# EC800M_CN.net
KiCad netlist of a schematic drawn in Altium Designer
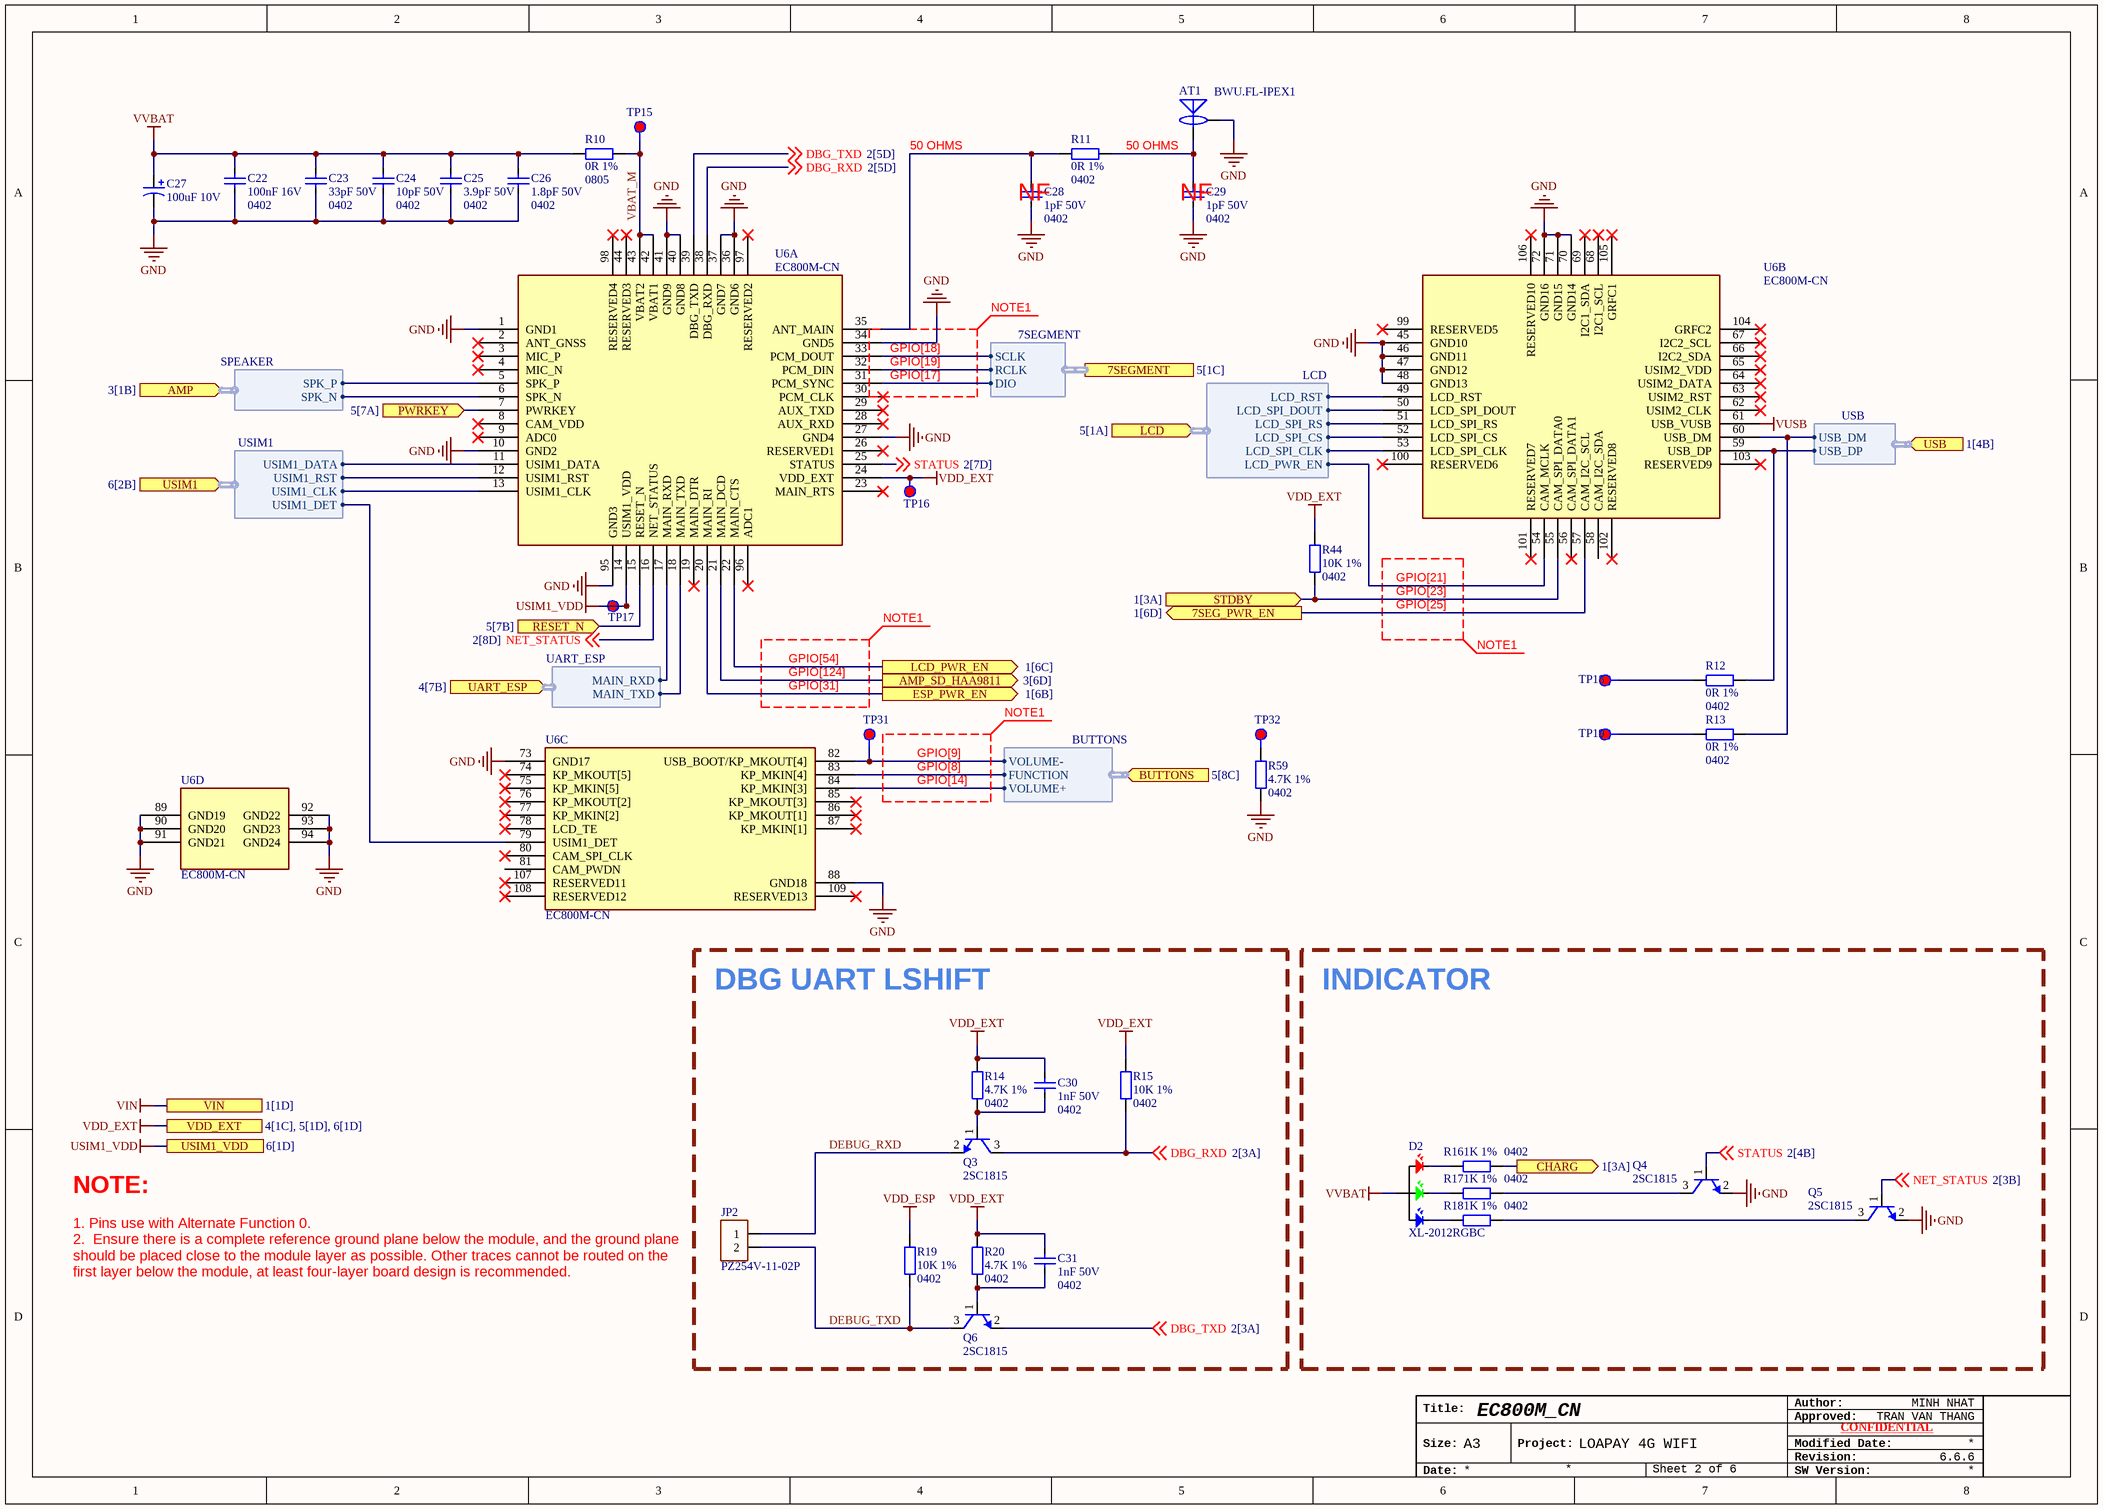
[diagram p0: EC800M_CN.SchDoc]

(export (version "E")
  (design (tool "Eeschema 10.0.6"))
  (components
    (comp (ref "AT1")
      (value "BWU.FL-IPEX1")
      (footprint "IPEX-SMD_BWIPX-1-001E")
      (description "1 Inner pin IPEX Board-End 1.25mm 6GHz 50Ω 2mm SMD Coaxial Connectors (RF) ROHS")
      (fields (field (name "MANUFACTURER") "BAT WIRELESS") (field (name "LCSC PART") "C5137195"))
      (libsource (lib "Antenna") (part "BAT WIRELESS BWU.FL-IPEX1"))
    )
    (comp (ref "C22")
      (value "100nF 16V")
      (footprint "C0402_2")
      (description "16V 100nF X7R ±10% 0402 Multilayer Ceramic Capacitors MLCC - SMD/SMT ROHS")
      (fields
        (field (name "MANUFACTURER") "YAGEO")
        (field (name "MANUFACTURE PART NUMBER") "CC0402KRX7R7BB104")
        (field (name "PACKAGE") "0402")
      )
      (libsource (lib "Capacitor") (part "C0402_MLCC_100nF_16V"))
    )
    (comp (ref "C23")
      (value "33pF 50V")
      (footprint "C0402_2")
      (description "50V 33pF NP0 ±5% 0402 Multilayer Ceramic Capacitors MLCC - SMD/SMT ROHS")
      (fields
        (field (name "MANUFACTURER") "YAGEO")
        (field (name "MANUFACTURE PART NUMBER") "CC0402JRNPO9BN330")
        (field (name "PACKAGE") "0402")
      )
      (libsource (lib "Capacitor") (part "C0402_MLCC_33pF_50V"))
    )
    (comp (ref "C24")
      (value "10pF 50V")
      (footprint "C0402_2")
      (description "50V 10pF C0G ±5% 0402 Multilayer Ceramic Capacitors MLCC - SMD/SMT ROHS")
      (fields
        (field (name "MANUFACTURER") "VIIYONG")
        (field (name "MANUFACTURE PART NUMBER") "V100J0402C0G500NBT")
        (field (name "PACKAGE") "0402")
      )
      (libsource (lib "Capacitor") (part "C0402_MLCC_10pF_50V"))
    )
    (comp (ref "C25")
      (value "3.9pF 50V")
      (footprint "C0402_2")
      (description "50V 3.9pF NP0 0402 Multilayer Ceramic Capacitors MLCC - SMD/SMT ROHS")
      (fields
        (field (name "MANUFACTURER") "YAGEO")
        (field (name "MANUFACTURE PART NUMBER") "CC0402BRNPO9BN3R9")
        (field (name "PACKAGE") "0402")
      )
      (libsource (lib "Capacitor") (part "C0402_MLCC_3.9pF_50V"))
    )
    (comp (ref "C26")
      (value "1.8pF 50V")
      (footprint "C0402_2")
      (description "50V 1.8pF C0G 0402 Multilayer Ceramic Capacitors MLCC - SMD/SMT ROHS")
      (fields
        (field (name "MANUFACTURER") "Murata Electronics")
        (field (name "MANUFACTURE PART NUMBER") "GJM1555C1H1R8WB01D")
        (field (name "PACKAGE") "0402")
      )
      (libsource (lib "Capacitor") (part "C0402_MLCC_1.8pF_50V"))
    )
    (comp (ref "C27")
      (value "100uF 10V")
      (footprint "CAP-ALU-SMD-C-NEW")
      (description "100uF 10V 49mA@120Hz ±20% SMD,D5xL5.4mm Aluminum Electrolytic Capacitors - SMD ROHS")
      (fields
        (field (name "MANUFACTURER") "ROQANG")
        (field (name "MANUFACTURE PART NUMBER") "CS1A101M-CRD54")
      )
      (libsource (lib "Capacitor") (part "C_ALU_100uF_10V_C"))
    )
    (comp (ref "C28")
      (value "1pF 50V")
      (footprint "C0402_2")
      (description "50V 1pF NP0 0402 Multilayer Ceramic Capacitors MLCC - SMD/SMT ROHS")
      (fields
        (field (name "MANUFACTURER") "Walsin Tech Corp")
        (field (name "MANUFACTURE PART NUMBER") "0402N1R0B500CT")
        (field (name "PACKAGE") "0402")
      )
      (libsource (lib "Capacitor") (part "C0402_MLCC_1pF_50V"))
    )
    (comp (ref "C29")
      (value "1pF 50V")
      (footprint "C0402_2")
      (description "50V 1pF NP0 0402 Multilayer Ceramic Capacitors MLCC - SMD/SMT ROHS")
      (fields
        (field (name "MANUFACTURER") "Walsin Tech Corp")
        (field (name "MANUFACTURE PART NUMBER") "0402N1R0B500CT")
        (field (name "PACKAGE") "0402")
      )
      (libsource (lib "Capacitor") (part "C0402_MLCC_1pF_50V"))
    )
    (comp (ref "C30")
      (value "1nF 50V")
      (footprint "C0402_2")
      (description "50V 1nF X7R ±10% 0402 Multilayer Ceramic Capacitors MLCC - SMD/SMT ROHS")
      (fields
        (field (name "MANUFACTURER") "Murata Electronics")
        (field (name "MANUFACTURE PART NUMBER") "GCM155R71H102KA37J")
        (field (name "PACKAGE") "0402")
      )
      (libsource (lib "Capacitor") (part "C0402_MLCC_1nF_50V"))
    )
    (comp (ref "C31")
      (value "1nF 50V")
      (footprint "C0402_2")
      (description "50V 1nF X7R ±10% 0402 Multilayer Ceramic Capacitors MLCC - SMD/SMT ROHS")
      (fields
        (field (name "MANUFACTURER") "Murata Electronics")
        (field (name "MANUFACTURE PART NUMBER") "GCM155R71H102KA37J")
        (field (name "PACKAGE") "0402")
      )
      (libsource (lib "Capacitor") (part "C0402_MLCC_1nF_50V"))
    )
    (comp (ref "D2")
      (value "XL-2012RGBC")
      (footprint "LED-SMD_4P-L2.0-W1.3-BR")
      (description "0805 RGB LEDs ROHS")
      (fields (field (name "MANUFACTURER") "XINGLIGHT") (field (name "LCSC PART") "C965848"))
      (libsource (lib "LED") (part "XL-2012RGBC"))
    )
    (comp (ref "JP2")
      (value "PZ254V-11-02P")
      (footprint "JP2_M - 2")
      (fields (field (name "MANUFACTURER") "XFCN") (field (name "LCSC PART") "C492401"))
      (libsource (lib "Connector") (part "PZ254V-11-02P"))
    )
    (comp (ref "Q3")
      (value "2SC1815")
      (footprint "TF_SOT_23_3")
      (description "50V 200mW 200@2mA,6V 150mA NPN SOT-23 Bipolar (BJT) ROHS")
      (fields (field (name "MANUFACTURER") "Guangdong Hottech") (field (name "LCSC PART") "C181171"))
      (libsource (lib "Trans_Fet") (part "2SC1815"))
    )
    (comp (ref "Q4")
      (value "2SC1815")
      (footprint "TF_SOT_23_3")
      (description "50V 200mW 200@2mA,6V 150mA NPN SOT-23 Bipolar (BJT) ROHS")
      (fields (field (name "MANUFACTURER") "Guangdong Hottech") (field (name "LCSC PART") "C181171"))
      (libsource (lib "Trans_Fet") (part "2SC1815"))
    )
    (comp (ref "Q5")
      (value "2SC1815")
      (footprint "TF_SOT_23_3")
      (description "50V 200mW 200@2mA,6V 150mA NPN SOT-23 Bipolar (BJT) ROHS")
      (fields (field (name "MANUFACTURER") "Guangdong Hottech") (field (name "LCSC PART") "C181171"))
      (libsource (lib "Trans_Fet") (part "2SC1815"))
    )
    (comp (ref "Q6")
      (value "2SC1815")
      (footprint "TF_SOT_23_3")
      (description "50V 200mW 200@2mA,6V 150mA NPN SOT-23 Bipolar (BJT) ROHS")
      (fields (field (name "MANUFACTURER") "Guangdong Hottech") (field (name "LCSC PART") "C181171"))
      (libsource (lib "Trans_Fet") (part "2SC1815"))
    )
    (comp (ref "R10")
      (value "0R 1%")
      (footprint "RES_SMD_0805")
      (description "0 Ohms Jumper Chip Resistor 0805 (2012 Metric) Moisture Resistant Thick Film")
      (fields
        (field (name "MANUFACTURER") "YAGEO")
        (field (name "MANUFACTURE PART NUMBER") "RC0805JR-070RL")
        (field (name "PACKAGE") "0805")
      )
      (libsource (lib "Resistor") (part "R0805_0R"))
    )
    (comp (ref "R11")
      (value "0R 1%")
      (footprint "RES_SMD_0402")
      (description "0 Ohms Jumper Chip Resistor 0402 (1005 Metric) Moisture Resistant Thick Film")
      (fields
        (field (name "MANUFACTURER") "YAGEO")
        (field (name "MANUFACTURE PART NUMBER") "RC0402JR-070RL")
        (field (name "PACKAGE") "0402")
      )
      (libsource (lib "Resistor") (part "R0402_0R"))
    )
    (comp (ref "R12")
      (value "0R 1%")
      (footprint "RES_SMD_0402")
      (description "0 Ohms Jumper Chip Resistor 0402 (1005 Metric) Moisture Resistant Thick Film")
      (fields
        (field (name "MANUFACTURER") "YAGEO")
        (field (name "MANUFACTURE PART NUMBER") "RC0402JR-070RL")
        (field (name "PACKAGE") "0402")
      )
      (libsource (lib "Resistor") (part "R0402_0R"))
    )
    (comp (ref "R13")
      (value "0R 1%")
      (footprint "RES_SMD_0402")
      (description "0 Ohms Jumper Chip Resistor 0402 (1005 Metric) Moisture Resistant Thick Film")
      (fields
        (field (name "MANUFACTURER") "YAGEO")
        (field (name "MANUFACTURE PART NUMBER") "RC0402JR-070RL")
        (field (name "PACKAGE") "0402")
      )
      (libsource (lib "Resistor") (part "R0402_0R"))
    )
    (comp (ref "R14")
      (value "4.7K 1%")
      (footprint "RES_SMD_0402")
      (description "4.7 kOhms ±1% 0.063W, 1/16W Chip Resistor 0402 (1005 Metric) Thick Film")
      (fields
        (field (name "MANUFACTURER") "YAGEO")
        (field (name "MANUFACTURE PART NUMBER") "RC0402FR-074K7P")
        (field (name "PACKAGE") "0402")
      )
      (libsource (lib "Resistor") (part "R0402_4.7K"))
    )
    (comp (ref "R15")
      (value "10K 1%")
      (footprint "RES_SMD_0402")
      (description "10 kOhms ±1% 0.063W, 1/16W Chip Resistor 0402 (1005 Metric) Moisture Resistant Thick Film")
      (fields
        (field (name "MANUFACTURER") "YAGEO")
        (field (name "MANUFACTURE PART NUMBER") "RC0402FR-0710KL")
        (field (name "PACKAGE") "0402")
      )
      (libsource (lib "Resistor") (part "R0402_10K"))
    )
    (comp (ref "R16")
      (value "1K 1%")
      (footprint "RES_SMD_0402")
      (description "1 kOhms ±1% 0.063W, 1/16W Chip Resistor 0402 (1005 Metric) Moisture Resistant Thick Film")
      (fields
        (field (name "MANUFACTURER") "YAGEO")
        (field (name "MANUFACTURE PART NUMBER") "RC0402FR-071KL")
        (field (name "PACKAGE") "0402")
      )
      (libsource (lib "Resistor") (part "R0402_1K"))
    )
    (comp (ref "R17")
      (value "1K 1%")
      (footprint "RES_SMD_0402")
      (description "1 kOhms ±1% 0.063W, 1/16W Chip Resistor 0402 (1005 Metric) Moisture Resistant Thick Film")
      (fields
        (field (name "MANUFACTURER") "YAGEO")
        (field (name "MANUFACTURE PART NUMBER") "RC0402FR-071KL")
        (field (name "PACKAGE") "0402")
      )
      (libsource (lib "Resistor") (part "R0402_1K"))
    )
    (comp (ref "R18")
      (value "1K 1%")
      (footprint "RES_SMD_0402")
      (description "1 kOhms ±1% 0.063W, 1/16W Chip Resistor 0402 (1005 Metric) Moisture Resistant Thick Film")
      (fields
        (field (name "MANUFACTURER") "YAGEO")
        (field (name "MANUFACTURE PART NUMBER") "RC0402FR-071KL")
        (field (name "PACKAGE") "0402")
      )
      (libsource (lib "Resistor") (part "R0402_1K"))
    )
    (comp (ref "R19")
      (value "10K 1%")
      (footprint "RES_SMD_0402")
      (description "10 kOhms ±1% 0.063W, 1/16W Chip Resistor 0402 (1005 Metric) Moisture Resistant Thick Film")
      (fields
        (field (name "MANUFACTURER") "YAGEO")
        (field (name "MANUFACTURE PART NUMBER") "RC0402FR-0710KL")
        (field (name "PACKAGE") "0402")
      )
      (libsource (lib "Resistor") (part "R0402_10K"))
    )
    (comp (ref "R20")
      (value "4.7K 1%")
      (footprint "RES_SMD_0402")
      (description "4.7 kOhms ±1% 0.063W, 1/16W Chip Resistor 0402 (1005 Metric) Thick Film")
      (fields
        (field (name "MANUFACTURER") "YAGEO")
        (field (name "MANUFACTURE PART NUMBER") "RC0402FR-074K7P")
        (field (name "PACKAGE") "0402")
      )
      (libsource (lib "Resistor") (part "R0402_4.7K"))
    )
    (comp (ref "R44")
      (value "10K 1%")
      (footprint "RES_SMD_0402")
      (description "10 kOhms ±1% 0.063W, 1/16W Chip Resistor 0402 (1005 Metric) Moisture Resistant Thick Film")
      (fields
        (field (name "MANUFACTURER") "YAGEO")
        (field (name "MANUFACTURE PART NUMBER") "RC0402FR-0710KL")
        (field (name "PACKAGE") "0402")
      )
      (libsource (lib "Resistor") (part "R0402_10K"))
    )
    (comp (ref "R59")
      (value "4.7K 1%")
      (footprint "RES_SMD_0402")
      (description "4.7 kOhms ±1% 0.063W, 1/16W Chip Resistor 0402 (1005 Metric) Thick Film")
      (fields
        (field (name "MANUFACTURER") "YAGEO")
        (field (name "MANUFACTURE PART NUMBER") "RC0402FR-074K7P")
        (field (name "PACKAGE") "0402")
      )
      (libsource (lib "Resistor") (part "R0402_4.7K"))
    )
    (comp (ref "TP15")
      (value "Test Point")
      (footprint "TEST_POINT")
      (libsource (lib "Connector") (part "TEST_POINT"))
    )
    (comp (ref "TP16")
      (value "Test Point")
      (footprint "TEST_POINT")
      (libsource (lib "Connector") (part "TEST_POINT"))
    )
    (comp (ref "TP17")
      (value "Test Point")
      (footprint "TEST_POINT")
      (libsource (lib "Connector") (part "TEST_POINT"))
    )
    (comp (ref "TP18")
      (value "Test Point")
      (footprint "TEST_POINT")
      (libsource (lib "Connector") (part "TEST_POINT"))
    )
    (comp (ref "TP19")
      (value "Test Point")
      (footprint "TEST_POINT")
      (libsource (lib "Connector") (part "TEST_POINT"))
    )
    (comp (ref "TP31")
      (value "Test Point")
      (footprint "TEST_POINT")
      (libsource (lib "Connector") (part "TEST_POINT"))
    )
    (comp (ref "TP32")
      (value "Test Point")
      (footprint "TEST_POINT")
      (libsource (lib "Connector") (part "TEST_POINT"))
    )
    (comp (ref "U6")
      (value "EC800M-CN")
      (footprint "ECM800-CN")
      (description "IoT/ M2M-optimized \r\nLTE Cat 1 Module")
      (fields (field (name "MANUFACTURER") "Quectel"))
      (libsource (lib "MCU") (part "EC800M-CN"))
    )
  )
  (nets
    (net (code "8") (name "/7SEG_PWR_EN") (class "Default")
      (node (ref "U6") (pin "57") (pinfunction "CAM_I2C_SCL_57") (pintype "passive"))
    )
    (net (code "9") (name "/AMP_SD_HAA9811") (class "Default")
      (node (ref "U6") (pin "21") (pinfunction "MAIN_DCD_21") (pintype "passive"))
    )
    (net (code "10") (name "/CHARG") (class "Default")
      (node (ref "R16") (pin "1") (pinfunction "1_1") (pintype "passive"))
    )
    (net (code "11") (name "/DEBUG_RXD") (class "Default")
      (node (ref "JP2") (pin "1") (pinfunction "1_1") (pintype "passive"))
      (node (ref "Q3") (pin "2") (pinfunction "E_2") (pintype "passive"))
    )
    (net (code "12") (name "/DEBUG_TXD") (class "Default")
      (node (ref "JP2") (pin "2") (pinfunction "2_2") (pintype "passive"))
      (node (ref "Q6") (pin "3") (pinfunction "C_3") (pintype "passive"))
      (node (ref "R19") (pin "1") (pinfunction "1_1") (pintype "passive"))
    )
    (net (code "13") (name "/DIO") (class "Default")
      (node (ref "U6") (pin "31") (pinfunction "PCM_SYNC_31") (pintype "passive"))
    )
    (net (code "14") (name "/ESP_PWR_EN") (class "Default")
      (node (ref "U6") (pin "20") (pinfunction "MAIN_RI_20") (pintype "passive"))
    )
    (net (code "15") (name "/FUNCTION") (class "Default")
      (node (ref "U6") (pin "83") (pinfunction "KP_MKIN[4]_83") (pintype "passive"))
    )
    (net (code "16") (name "/LCD_PWR_EN") (class "Default")
      (node (ref "U6") (pin "22") (pinfunction "MAIN_CTS_22") (pintype "passive"))
    )
    (net (code "17") (name "/LCD_RST") (class "Default")
      (node (ref "U6") (pin "49") (pinfunction "LCD_RST_49") (pintype "passive"))
    )
    (net (code "18") (name "/LCD_SPI_CLK") (class "Default")
      (node (ref "U6") (pin "53") (pinfunction "LCD_SPI_CLK_53") (pintype "passive"))
    )
    (net (code "19") (name "/LCD_SPI_CS") (class "Default")
      (node (ref "U6") (pin "52") (pinfunction "LCD_SPI_CS_52") (pintype "passive"))
    )
    (net (code "20") (name "/LCD_SPI_DOUT") (class "Default")
      (node (ref "U6") (pin "50") (pinfunction "LCD_SPI_DOUT_50") (pintype "passive"))
    )
    (net (code "21") (name "/LCD_SPI_RS") (class "Default")
      (node (ref "U6") (pin "51") (pinfunction "LCD_SPI_RS_51") (pintype "passive"))
    )
    (net (code "22") (name "/MAIN_RXD") (class "Default")
      (node (ref "U6") (pin "17") (pinfunction "MAIN_RXD_17") (pintype "passive"))
    )
    (net (code "23") (name "/MAIN_TXD") (class "Default")
      (node (ref "U6") (pin "18") (pinfunction "MAIN_TXD_18") (pintype "passive"))
    )
    (net (code "24") (name "/PWRKEY") (class "Default")
      (node (ref "U6") (pin "7") (pinfunction "PWRKEY_7") (pintype "passive"))
    )
    (net (code "25") (name "/RCLK") (class "Default")
      (node (ref "U6") (pin "32") (pinfunction "PCM_DIN_32") (pintype "passive"))
    )
    (net (code "26") (name "/RESET_N") (class "Default")
      (node (ref "U6") (pin "15") (pinfunction "RESET_N_15") (pintype "passive"))
    )
    (net (code "27") (name "/SCLK") (class "Default")
      (node (ref "U6") (pin "33") (pinfunction "PCM_DOUT_33") (pintype "passive"))
    )
    (net (code "28") (name "/SPK_N") (class "Default")
      (node (ref "U6") (pin "6") (pinfunction "SPK_N_6") (pintype "passive"))
    )
    (net (code "29") (name "/SPK_P") (class "Default")
      (node (ref "U6") (pin "5") (pinfunction "SPK_P_5") (pintype "passive"))
    )
    (net (code "30") (name "/STDBY") (class "Default")
      (node (ref "R44") (pin "1") (pinfunction "1_1") (pintype "passive"))
      (node (ref "U6") (pin "55") (pinfunction "CAM_SPI_DATA0_55") (pintype "passive"))
    )
    (net (code "31") (name "/USB_DM") (class "Default")
      (node (ref "R13") (pin "2") (pinfunction "2_2") (pintype "passive"))
      (node (ref "U6") (pin "60") (pinfunction "USB_DM_60") (pintype "passive"))
    )
    (net (code "32") (name "/USB_DP") (class "Default")
      (node (ref "R12") (pin "2") (pinfunction "2_2") (pintype "passive"))
      (node (ref "U6") (pin "59") (pinfunction "USB_DP_59") (pintype "passive"))
    )
    (net (code "33") (name "/USIM1_CLK") (class "Default")
      (node (ref "U6") (pin "13") (pinfunction "USIM1_CLK_13") (pintype "passive"))
    )
    (net (code "34") (name "/USIM1_DATA") (class "Default")
      (node (ref "U6") (pin "11") (pinfunction "USIM1_DATA_11") (pintype "passive"))
    )
    (net (code "35") (name "/USIM1_DET") (class "Default")
      (node (ref "U6") (pin "79") (pinfunction "USIM1_DET_79") (pintype "passive"))
    )
    (net (code "36") (name "/USIM1_RST") (class "Default")
      (node (ref "U6") (pin "12") (pinfunction "USIM1_RST_12") (pintype "passive"))
    )
    (net (code "37") (name "/VBAT_M") (class "Default")
      (node (ref "R10") (pin "2") (pinfunction "2_2") (pintype "passive"))
      (node (ref "TP15") (pin "1") (pinfunction "1_1") (pintype "passive"))
      (node (ref "U6") (pin "42") (pinfunction "VBAT1_42") (pintype "passive"))
      (node (ref "U6") (pin "43") (pinfunction "VBAT2_43") (pintype "passive"))
    )
    (net (code "38") (name "/VOLUME+") (class "Default")
      (node (ref "U6") (pin "84") (pinfunction "KP_MKIN[3]_84") (pintype "passive"))
    )
    (net (code "39") (name "/VOLUME-") (class "Default")
      (node (ref "TP31") (pin "1") (pinfunction "1_1") (pintype "passive"))
      (node (ref "U6") (pin "82") (pinfunction "USB_BOOT/KP_MKOUT[4]_82") (pintype "passive"))
    )
    (net (code "47") (name "DBG_RXD") (class "Default")
      (node (ref "Q3") (pin "3") (pinfunction "C_3") (pintype "passive"))
      (node (ref "R15") (pin "1") (pinfunction "1_1") (pintype "passive"))
      (node (ref "U6") (pin "38") (pinfunction "DBG_RXD_38") (pintype "passive"))
    )
    (net (code "48") (name "DBG_TXD") (class "Default")
      (node (ref "Q6") (pin "2") (pinfunction "E_2") (pintype "passive"))
      (node (ref "U6") (pin "39") (pinfunction "DBG_TXD_39") (pintype "passive"))
    )
    (net (code "49") (name "GND") (class "Default")
      (node (ref "AT1") (pin "2") (pinfunction "2_2") (pintype "passive"))
      (node (ref "C22") (pin "1") (pinfunction "1_1") (pintype "passive"))
      (node (ref "C23") (pin "1") (pinfunction "1_1") (pintype "passive"))
      (node (ref "C24") (pin "1") (pinfunction "1_1") (pintype "passive"))
      (node (ref "C25") (pin "1") (pinfunction "1_1") (pintype "passive"))
      (node (ref "C26") (pin "1") (pinfunction "1_1") (pintype "passive"))
      (node (ref "C27") (pin "2") (pinfunction "2_2") (pintype "passive"))
      (node (ref "C28") (pin "1") (pinfunction "1_1") (pintype "passive"))
      (node (ref "C29") (pin "1") (pinfunction "1_1") (pintype "passive"))
      (node (ref "Q4") (pin "2") (pinfunction "E_2") (pintype "passive"))
      (node (ref "Q5") (pin "2") (pinfunction "E_2") (pintype "passive"))
      (node (ref "R59") (pin "1") (pinfunction "1_1") (pintype "passive"))
      (node (ref "U6") (pin "1") (pinfunction "GND1_1") (pintype "passive"))
      (node (ref "U6") (pin "10") (pinfunction "GND2_10") (pintype "passive"))
      (node (ref "U6") (pin "27") (pinfunction "GND4_27") (pintype "passive"))
      (node (ref "U6") (pin "34") (pinfunction "GND5_34") (pintype "passive"))
      (node (ref "U6") (pin "36") (pinfunction "GND6_36") (pintype "passive"))
      (node (ref "U6") (pin "37") (pinfunction "GND7_37") (pintype "passive"))
      (node (ref "U6") (pin "40") (pinfunction "GND8_40") (pintype "passive"))
      (node (ref "U6") (pin "41") (pinfunction "GND9_41") (pintype "passive"))
      (node (ref "U6") (pin "45") (pinfunction "GND10_45") (pintype "passive"))
      (node (ref "U6") (pin "46") (pinfunction "GND11_46") (pintype "passive"))
      (node (ref "U6") (pin "47") (pinfunction "GND12_47") (pintype "passive"))
      (node (ref "U6") (pin "48") (pinfunction "GND13_48") (pintype "passive"))
      (node (ref "U6") (pin "70") (pinfunction "GND14_70") (pintype "passive"))
      (node (ref "U6") (pin "71") (pinfunction "GND15_71") (pintype "passive"))
      (node (ref "U6") (pin "72") (pinfunction "GND16_72") (pintype "passive"))
      (node (ref "U6") (pin "73") (pinfunction "GND17_73") (pintype "passive"))
      (node (ref "U6") (pin "88") (pinfunction "GND18_88") (pintype "passive"))
      (node (ref "U6") (pin "89") (pinfunction "GND19_89") (pintype "passive"))
      (node (ref "U6") (pin "90") (pinfunction "GND20_90") (pintype "passive"))
      (node (ref "U6") (pin "91") (pinfunction "GND21_91") (pintype "passive"))
      (node (ref "U6") (pin "92") (pinfunction "GND22_92") (pintype "passive"))
      (node (ref "U6") (pin "93") (pinfunction "GND23_93") (pintype "passive"))
      (node (ref "U6") (pin "94") (pinfunction "GND24_94") (pintype "passive"))
      (node (ref "U6") (pin "95") (pinfunction "GND3_95") (pintype "passive"))
    )
    (net (code "50") (name "NET_STATUS") (class "Default")
      (node (ref "Q5") (pin "1") (pinfunction "B_1") (pintype "passive"))
      (node (ref "U6") (pin "16") (pinfunction "NET_STATUS_16") (pintype "passive"))
    )
    (net (code "51") (name "Net-(AT1-Pad1)") (class "Default")
      (node (ref "AT1") (pin "1") (pinfunction "1_1") (pintype "passive"))
      (node (ref "C29") (pin "2") (pinfunction "2_2") (pintype "passive"))
      (node (ref "R11") (pin "2") (pinfunction "2_2") (pintype "passive"))
    )
    (net (code "52") (name "Net-(D2-Pad1)") (class "Default")
      (node (ref "D2") (pin "1") (pinfunction "1_1") (pintype "passive"))
      (node (ref "R16") (pin "2") (pinfunction "2_2") (pintype "passive"))
    )
    (net (code "53") (name "Net-(D2-Pad2)") (class "Default")
      (node (ref "D2") (pin "2") (pinfunction "2_2") (pintype "passive"))
      (node (ref "R17") (pin "2") (pinfunction "2_2") (pintype "passive"))
    )
    (net (code "54") (name "Net-(D2-Pad4)") (class "Default")
      (node (ref "D2") (pin "4") (pinfunction "4_4") (pintype "passive"))
      (node (ref "R18") (pin "2") (pinfunction "2_2") (pintype "passive"))
    )
    (net (code "55") (name "Net-(Q3-B)") (class "Default")
      (node (ref "C30") (pin "1") (pinfunction "1_1") (pintype "passive"))
      (node (ref "Q3") (pin "1") (pinfunction "B_1") (pintype "passive"))
      (node (ref "R14") (pin "1") (pinfunction "1_1") (pintype "passive"))
    )
    (net (code "56") (name "Net-(Q4-C)") (class "Default")
      (node (ref "Q4") (pin "3") (pinfunction "C_3") (pintype "passive"))
      (node (ref "R17") (pin "1") (pinfunction "1_1") (pintype "passive"))
    )
    (net (code "57") (name "Net-(Q5-C)") (class "Default")
      (node (ref "Q5") (pin "3") (pinfunction "C_3") (pintype "passive"))
      (node (ref "R18") (pin "1") (pinfunction "1_1") (pintype "passive"))
    )
    (net (code "58") (name "Net-(Q6-B)") (class "Default")
      (node (ref "C31") (pin "1") (pinfunction "1_1") (pintype "passive"))
      (node (ref "Q6") (pin "1") (pinfunction "B_1") (pintype "passive"))
      (node (ref "R20") (pin "1") (pinfunction "1_1") (pintype "passive"))
    )
    (net (code "59") (name "Net-(R12-Pad1)") (class "Default")
      (node (ref "R12") (pin "1") (pinfunction "1_1") (pintype "passive"))
      (node (ref "TP18") (pin "1") (pinfunction "1_1") (pintype "passive"))
    )
    (net (code "60") (name "Net-(R13-Pad1)") (class "Default")
      (node (ref "R13") (pin "1") (pinfunction "1_1") (pintype "passive"))
      (node (ref "TP19") (pin "1") (pinfunction "1_1") (pintype "passive"))
    )
    (net (code "61") (name "Net-(R59-Pad2)") (class "Default")
      (node (ref "R59") (pin "2") (pinfunction "2_2") (pintype "passive"))
      (node (ref "TP32") (pin "1") (pinfunction "1_1") (pintype "passive"))
    )
    (net (code "62") (name "Net-(U6A-ANT_MAIN)") (class "Default")
      (node (ref "C28") (pin "2") (pinfunction "2_2") (pintype "passive"))
      (node (ref "R11") (pin "1") (pinfunction "1_1") (pintype "passive"))
      (node (ref "U6") (pin "35") (pinfunction "ANT_MAIN_35") (pintype "passive"))
    )
    (net (code "63") (name "STATUS") (class "Default")
      (node (ref "Q4") (pin "1") (pinfunction "B_1") (pintype "passive"))
      (node (ref "U6") (pin "25") (pinfunction "STATUS_25") (pintype "passive"))
    )
    (net (code "64") (name "USIM1_VDD") (class "Default")
      (node (ref "TP17") (pin "1") (pinfunction "1_1") (pintype "passive"))
      (node (ref "U6") (pin "14") (pinfunction "USIM1_VDD_14") (pintype "passive"))
    )
    (net (code "65") (name "VDD_ESP") (class "Default")
      (node (ref "R19") (pin "2") (pinfunction "2_2") (pintype "passive"))
    )
    (net (code "66") (name "VDD_EXT") (class "Default")
      (node (ref "C30") (pin "2") (pinfunction "2_2") (pintype "passive"))
      (node (ref "C31") (pin "2") (pinfunction "2_2") (pintype "passive"))
      (node (ref "R14") (pin "2") (pinfunction "2_2") (pintype "passive"))
      (node (ref "R15") (pin "2") (pinfunction "2_2") (pintype "passive"))
      (node (ref "R20") (pin "2") (pinfunction "2_2") (pintype "passive"))
      (node (ref "R44") (pin "2") (pinfunction "2_2") (pintype "passive"))
      (node (ref "TP16") (pin "1") (pinfunction "1_1") (pintype "passive"))
      (node (ref "U6") (pin "24") (pinfunction "VDD_EXT_24") (pintype "passive"))
    )
    (net (code "68") (name "VUSB") (class "Default")
      (node (ref "U6") (pin "61") (pinfunction "USB_VUSB_61") (pintype "passive"))
    )
    (net (code "69") (name "VVBAT") (class "Default")
      (node (ref "C22") (pin "2") (pinfunction "2_2") (pintype "passive"))
      (node (ref "C23") (pin "2") (pinfunction "2_2") (pintype "passive"))
      (node (ref "C24") (pin "2") (pinfunction "2_2") (pintype "passive"))
      (node (ref "C25") (pin "2") (pinfunction "2_2") (pintype "passive"))
      (node (ref "C26") (pin "2") (pinfunction "2_2") (pintype "passive"))
      (node (ref "C27") (pin "1") (pinfunction "1_1") (pintype "passive"))
      (node (ref "D2") (pin "3") (pinfunction "3_3") (pintype "passive"))
      (node (ref "R10") (pin "1") (pinfunction "1_1") (pintype "passive"))
    )
    (net (code "70") (name "unconnected-(U6A-ADC0-Pad9)") (class "Default")
      (node (ref "U6") (pin "9") (pinfunction "ADC0_9") (pintype "passive+no_connect"))
    )
    (net (code "71") (name "unconnected-(U6A-ADC1-Pad96)") (class "Default")
      (node (ref "U6") (pin "96") (pinfunction "ADC1_96") (pintype "passive+no_connect"))
    )
    (net (code "72") (name "unconnected-(U6A-ANT_GNSS-Pad2)") (class "Default")
      (node (ref "U6") (pin "2") (pinfunction "ANT_GNSS_2") (pintype "passive+no_connect"))
    )
    (net (code "73") (name "unconnected-(U6A-AUX_RXD-Pad28)") (class "Default")
      (node (ref "U6") (pin "28") (pinfunction "AUX_RXD_28") (pintype "passive+no_connect"))
    )
    (net (code "74") (name "unconnected-(U6A-AUX_TXD-Pad29)") (class "Default")
      (node (ref "U6") (pin "29") (pinfunction "AUX_TXD_29") (pintype "passive+no_connect"))
    )
    (net (code "75") (name "unconnected-(U6A-CAM_VDD-Pad8)") (class "Default")
      (node (ref "U6") (pin "8") (pinfunction "CAM_VDD_8") (pintype "passive+no_connect"))
    )
    (net (code "76") (name "unconnected-(U6A-MAIN_DTR-Pad19)") (class "Default")
      (node (ref "U6") (pin "19") (pinfunction "MAIN_DTR_19") (pintype "passive+no_connect"))
    )
    (net (code "77") (name "unconnected-(U6A-MAIN_RTS-Pad23)") (class "Default")
      (node (ref "U6") (pin "23") (pinfunction "MAIN_RTS_23") (pintype "passive+no_connect"))
    )
    (net (code "78") (name "unconnected-(U6A-MIC_N-Pad4)") (class "Default")
      (node (ref "U6") (pin "4") (pinfunction "MIC_N_4") (pintype "passive+no_connect"))
    )
    (net (code "79") (name "unconnected-(U6A-MIC_P-Pad3)") (class "Default")
      (node (ref "U6") (pin "3") (pinfunction "MIC_P_3") (pintype "passive+no_connect"))
    )
    (net (code "80") (name "unconnected-(U6A-PCM_CLK-Pad30)") (class "Default")
      (node (ref "U6") (pin "30") (pinfunction "PCM_CLK_30") (pintype "passive+no_connect"))
    )
    (net (code "81") (name "unconnected-(U6A-RESERVED1-Pad26)") (class "Default")
      (node (ref "U6") (pin "26") (pinfunction "RESERVED1_26") (pintype "passive+no_connect"))
    )
    (net (code "82") (name "unconnected-(U6A-RESERVED2-Pad97)") (class "Default")
      (node (ref "U6") (pin "97") (pinfunction "RESERVED2_97") (pintype "passive+no_connect"))
    )
    (net (code "83") (name "unconnected-(U6A-RESERVED3-Pad44)") (class "Default")
      (node (ref "U6") (pin "44") (pinfunction "RESERVED3_44") (pintype "passive+no_connect"))
    )
    (net (code "84") (name "unconnected-(U6A-RESERVED4-Pad98)") (class "Default")
      (node (ref "U6") (pin "98") (pinfunction "RESERVED4_98") (pintype "passive+no_connect"))
    )
    (net (code "85") (name "unconnected-(U6B-CAM_I2C_SDA-Pad58)") (class "Default")
      (node (ref "U6") (pin "58") (pinfunction "CAM_I2C_SDA_58") (pintype "passive"))
    )
    (net (code "86") (name "unconnected-(U6B-CAM_MCLK-Pad54)") (class "Default")
      (node (ref "U6") (pin "54") (pinfunction "CAM_MCLK_54") (pintype "passive"))
    )
    (net (code "87") (name "unconnected-(U6B-CAM_SPI_DATA1-Pad56)") (class "Default")
      (node (ref "U6") (pin "56") (pinfunction "CAM_SPI_DATA1_56") (pintype "passive+no_connect"))
    )
    (net (code "88") (name "unconnected-(U6B-GRFC1-Pad105)") (class "Default")
      (node (ref "U6") (pin "105") (pinfunction "GRFC1_105") (pintype "passive+no_connect"))
    )
    (net (code "89") (name "unconnected-(U6B-GRFC2-Pad104)") (class "Default")
      (node (ref "U6") (pin "104") (pinfunction "GRFC2_104") (pintype "passive+no_connect"))
    )
    (net (code "90") (name "unconnected-(U6B-I2C1_SCL-Pad68)") (class "Default")
      (node (ref "U6") (pin "68") (pinfunction "I2C1_SCL_68") (pintype "passive+no_connect"))
    )
    (net (code "91") (name "unconnected-(U6B-I2C1_SDA-Pad69)") (class "Default")
      (node (ref "U6") (pin "69") (pinfunction "I2C1_SDA_69") (pintype "passive+no_connect"))
    )
    (net (code "92") (name "unconnected-(U6B-I2C2_SCL-Pad67)") (class "Default")
      (node (ref "U6") (pin "67") (pinfunction "I2C2_SCL_67") (pintype "passive+no_connect"))
    )
    (net (code "93") (name "unconnected-(U6B-I2C2_SDA-Pad66)") (class "Default")
      (node (ref "U6") (pin "66") (pinfunction "I2C2_SDA_66") (pintype "passive+no_connect"))
    )
    (net (code "94") (name "unconnected-(U6B-RESERVED5-Pad99)") (class "Default")
      (node (ref "U6") (pin "99") (pinfunction "RESERVED5_99") (pintype "passive+no_connect"))
    )
    (net (code "95") (name "unconnected-(U6B-RESERVED6-Pad100)") (class "Default")
      (node (ref "U6") (pin "100") (pinfunction "RESERVED6_100") (pintype "passive+no_connect"))
    )
    (net (code "96") (name "unconnected-(U6B-RESERVED7-Pad101)") (class "Default")
      (node (ref "U6") (pin "101") (pinfunction "RESERVED7_101") (pintype "passive+no_connect"))
    )
    (net (code "97") (name "unconnected-(U6B-RESERVED8-Pad102)") (class "Default")
      (node (ref "U6") (pin "102") (pinfunction "RESERVED8_102") (pintype "passive+no_connect"))
    )
    (net (code "98") (name "unconnected-(U6B-RESERVED9-Pad103)") (class "Default")
      (node (ref "U6") (pin "103") (pinfunction "RESERVED9_103") (pintype "passive+no_connect"))
    )
    (net (code "99") (name "unconnected-(U6B-RESERVED10-Pad106)") (class "Default")
      (node (ref "U6") (pin "106") (pinfunction "RESERVED10_106") (pintype "passive+no_connect"))
    )
    (net (code "100") (name "unconnected-(U6B-USIM2_CLK-Pad62)") (class "Default")
      (node (ref "U6") (pin "62") (pinfunction "USIM2_CLK_62") (pintype "passive+no_connect"))
    )
    (net (code "101") (name "unconnected-(U6B-USIM2_DATA-Pad64)") (class "Default")
      (node (ref "U6") (pin "64") (pinfunction "USIM2_DATA_64") (pintype "passive+no_connect"))
    )
    (net (code "102") (name "unconnected-(U6B-USIM2_RST-Pad63)") (class "Default")
      (node (ref "U6") (pin "63") (pinfunction "USIM2_RST_63") (pintype "passive+no_connect"))
    )
    (net (code "103") (name "unconnected-(U6B-USIM2_VDD-Pad65)") (class "Default")
      (node (ref "U6") (pin "65") (pinfunction "USIM2_VDD_65") (pintype "passive+no_connect"))
    )
    (net (code "104") (name "unconnected-(U6C-CAM_PWDN-Pad81)") (class "Default")
      (node (ref "U6") (pin "81") (pinfunction "CAM_PWDN_81") (pintype "passive"))
    )
    (net (code "105") (name "unconnected-(U6C-CAM_SPI_CLK-Pad80)") (class "Default")
      (node (ref "U6") (pin "80") (pinfunction "CAM_SPI_CLK_80") (pintype "passive+no_connect"))
    )
    (net (code "106") (name "unconnected-(U6C-KP_MKIN[1]-Pad87)") (class "Default")
      (node (ref "U6") (pin "87") (pinfunction "KP_MKIN[1]_87") (pintype "passive+no_connect"))
    )
    (net (code "107") (name "unconnected-(U6C-KP_MKIN[2]-Pad77)") (class "Default")
      (node (ref "U6") (pin "77") (pinfunction "KP_MKIN[2]_77") (pintype "passive+no_connect"))
    )
    (net (code "108") (name "unconnected-(U6C-KP_MKIN[5]-Pad75)") (class "Default")
      (node (ref "U6") (pin "75") (pinfunction "KP_MKIN[5]_75") (pintype "passive+no_connect"))
    )
    (net (code "109") (name "unconnected-(U6C-KP_MKOUT[1]-Pad86)") (class "Default")
      (node (ref "U6") (pin "86") (pinfunction "KP_MKOUT[1]_86") (pintype "passive+no_connect"))
    )
    (net (code "110") (name "unconnected-(U6C-KP_MKOUT[2]-Pad76)") (class "Default")
      (node (ref "U6") (pin "76") (pinfunction "KP_MKOUT[2]_76") (pintype "passive+no_connect"))
    )
    (net (code "111") (name "unconnected-(U6C-KP_MKOUT[3]-Pad85)") (class "Default")
      (node (ref "U6") (pin "85") (pinfunction "KP_MKOUT[3]_85") (pintype "passive+no_connect"))
    )
    (net (code "112") (name "unconnected-(U6C-KP_MKOUT[5]-Pad74)") (class "Default")
      (node (ref "U6") (pin "74") (pinfunction "KP_MKOUT[5]_74") (pintype "passive+no_connect"))
    )
    (net (code "113") (name "unconnected-(U6C-LCD_TE-Pad78)") (class "Default")
      (node (ref "U6") (pin "78") (pinfunction "LCD_TE_78") (pintype "passive+no_connect"))
    )
    (net (code "114") (name "unconnected-(U6C-RESERVED11-Pad107)") (class "Default")
      (node (ref "U6") (pin "107") (pinfunction "RESERVED11_107") (pintype "passive+no_connect"))
    )
    (net (code "115") (name "unconnected-(U6C-RESERVED12-Pad108)") (class "Default")
      (node (ref "U6") (pin "108") (pinfunction "RESERVED12_108") (pintype "passive+no_connect"))
    )
    (net (code "116") (name "unconnected-(U6C-RESERVED13-Pad109)") (class "Default")
      (node (ref "U6") (pin "109") (pinfunction "RESERVED13_109") (pintype "passive+no_connect"))
    )
  )
)
